# PB_ExtenderPlug.net
KiCad netlist of a schematic drawn in Altium Designer
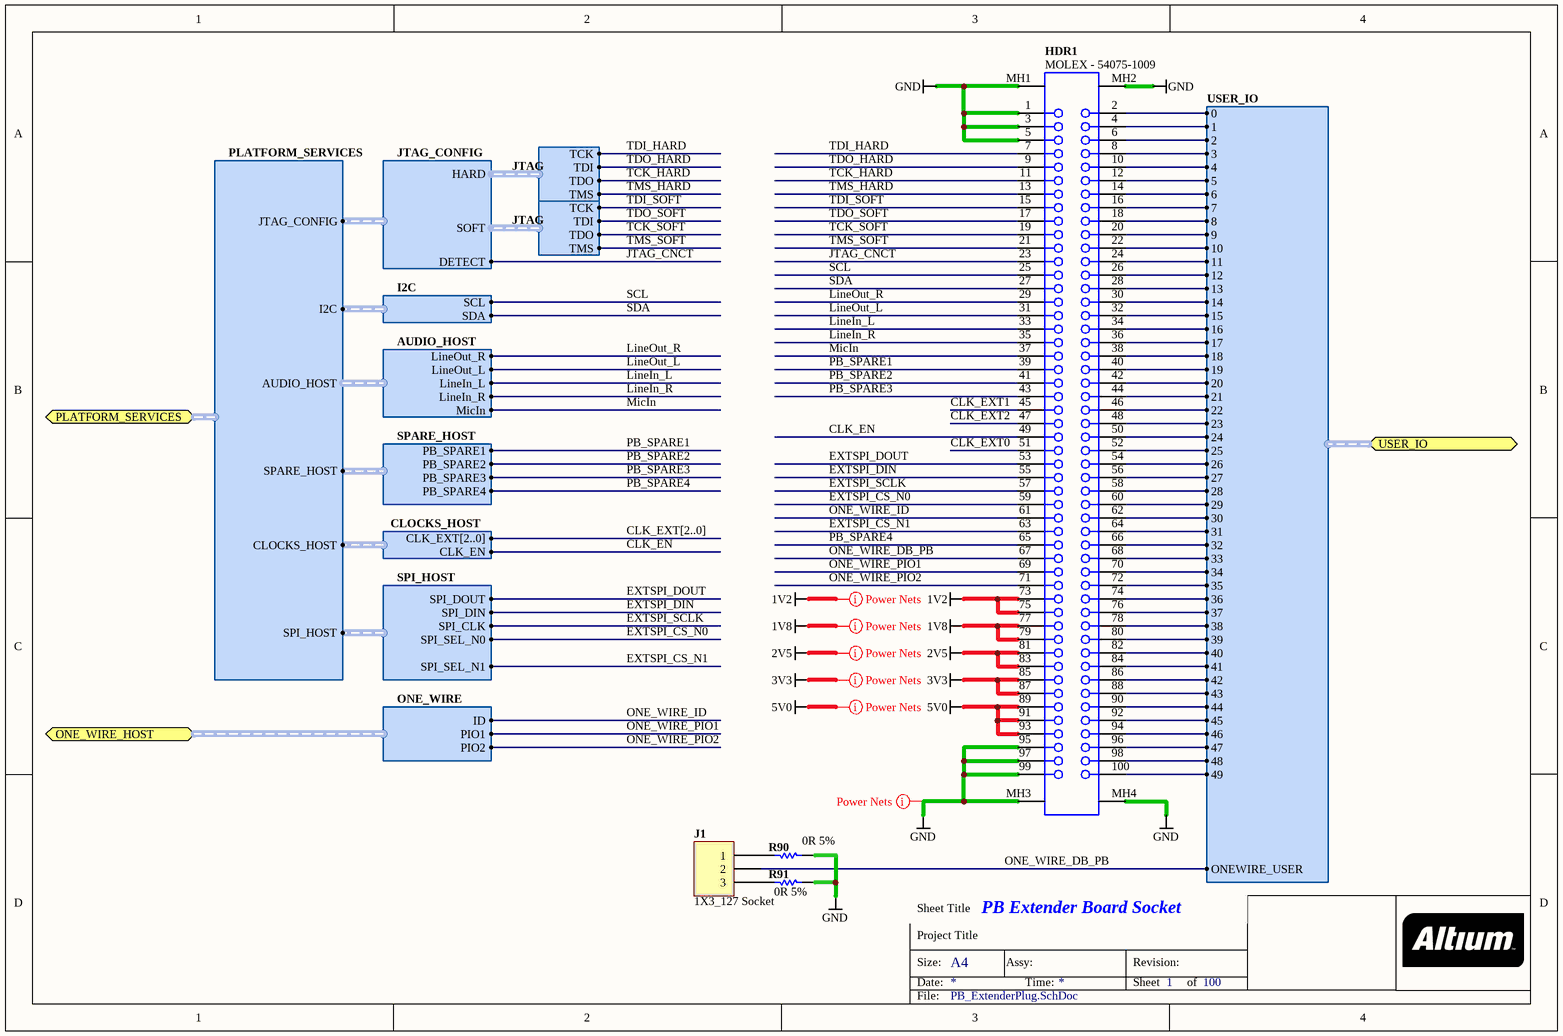
[diagram p0: PB_ExtenderPlug.SchDoc]

(export (version "E")
  (design (tool "Eeschema 10.0.6"))
  (components
    (comp (ref "HDR1")
      (value "MOLEX - 54075-1009")
      (footprint "54075")
      (description "Connector, Molex Docking Station 100 Pin Male 54075")
      (libsource (lib "AltiumDesignLibrary") (part "CON-DOCKSTAT-100-M-STR"))
    )
    (comp (ref "J1")
      (value "1X3_127 Socket")
      (footprint "MHDR1X3_127")
      (description "1X3 Pin Vert 1.27mm Socket")
      (fields (field (name "PUBLISHER") "Altium Limited"))
      (libsource (lib "AltiumDesignLibrary") (part "MHDR1X3_127"))
    )
    (comp (ref "R90")
      (value "0R 5%")
      (footprint "RESC1005-STAR")
      (description "Resistor, 0R 5% 0402 (1005)")
      (fields (field (name "TOLERANCE") "5 %"))
      (libsource (lib "AltiumDesignLibrary") (part "RES"))
    )
    (comp (ref "R91")
      (value "0R 5%")
      (footprint "RESC1005-STAR")
      (description "Resistor, 0R 5% 0402 (1005)")
      (fields (field (name "TOLERANCE") "5 %"))
      (libsource (lib "AltiumDesignLibrary") (part "RES"))
    )
  )
  (nets
    (net (code "10") (name "/0") (class "Default")
      (node (ref "HDR1") (pin "2") (pinfunction "2_2") (pintype "passive"))
    )
    (net (code "11") (name "/1") (class "Default")
      (node (ref "HDR1") (pin "4") (pinfunction "4_4") (pintype "passive"))
    )
    (net (code "12") (name "/2") (class "Default")
      (node (ref "HDR1") (pin "6") (pinfunction "6_6") (pintype "passive"))
    )
    (net (code "13") (name "/3") (class "Default")
      (node (ref "HDR1") (pin "8") (pinfunction "8_8") (pintype "passive"))
    )
    (net (code "14") (name "/4") (class "Default")
      (node (ref "HDR1") (pin "10") (pinfunction "10_10") (pintype "passive"))
    )
    (net (code "15") (name "/5") (class "Default")
      (node (ref "HDR1") (pin "12") (pinfunction "12_12") (pintype "passive"))
    )
    (net (code "16") (name "/6") (class "Default")
      (node (ref "HDR1") (pin "14") (pinfunction "14_14") (pintype "passive"))
    )
    (net (code "17") (name "/7") (class "Default")
      (node (ref "HDR1") (pin "16") (pinfunction "16_16") (pintype "passive"))
    )
    (net (code "18") (name "/8") (class "Default")
      (node (ref "HDR1") (pin "18") (pinfunction "18_18") (pintype "passive"))
    )
    (net (code "19") (name "/9") (class "Default")
      (node (ref "HDR1") (pin "20") (pinfunction "20_20") (pintype "passive"))
    )
    (net (code "20") (name "/10") (class "Default")
      (node (ref "HDR1") (pin "22") (pinfunction "22_22") (pintype "passive"))
    )
    (net (code "21") (name "/11") (class "Default")
      (node (ref "HDR1") (pin "24") (pinfunction "24_24") (pintype "passive"))
    )
    (net (code "22") (name "/12") (class "Default")
      (node (ref "HDR1") (pin "26") (pinfunction "26_26") (pintype "passive"))
    )
    (net (code "23") (name "/13") (class "Default")
      (node (ref "HDR1") (pin "28") (pinfunction "28_28") (pintype "passive"))
    )
    (net (code "24") (name "/14") (class "Default")
      (node (ref "HDR1") (pin "30") (pinfunction "30_30") (pintype "passive"))
    )
    (net (code "25") (name "/15") (class "Default")
      (node (ref "HDR1") (pin "32") (pinfunction "32_32") (pintype "passive"))
    )
    (net (code "26") (name "/16") (class "Default")
      (node (ref "HDR1") (pin "34") (pinfunction "34_34") (pintype "passive"))
    )
    (net (code "27") (name "/17") (class "Default")
      (node (ref "HDR1") (pin "36") (pinfunction "36_36") (pintype "passive"))
    )
    (net (code "28") (name "/18") (class "Default")
      (node (ref "HDR1") (pin "38") (pinfunction "38_38") (pintype "passive"))
    )
    (net (code "29") (name "/19") (class "Default")
      (node (ref "HDR1") (pin "40") (pinfunction "40_40") (pintype "passive"))
    )
    (net (code "30") (name "/20") (class "Default")
      (node (ref "HDR1") (pin "42") (pinfunction "42_42") (pintype "passive"))
    )
    (net (code "31") (name "/21") (class "Default")
      (node (ref "HDR1") (pin "44") (pinfunction "44_44") (pintype "passive"))
    )
    (net (code "32") (name "/22") (class "Default")
      (node (ref "HDR1") (pin "46") (pinfunction "46_46") (pintype "passive"))
    )
    (net (code "33") (name "/23") (class "Default")
      (node (ref "HDR1") (pin "48") (pinfunction "48_48") (pintype "passive"))
    )
    (net (code "34") (name "/24") (class "Default")
      (node (ref "HDR1") (pin "50") (pinfunction "50_50") (pintype "passive"))
    )
    (net (code "35") (name "/25") (class "Default")
      (node (ref "HDR1") (pin "52") (pinfunction "52_52") (pintype "passive"))
    )
    (net (code "36") (name "/26") (class "Default")
      (node (ref "HDR1") (pin "54") (pinfunction "54_54") (pintype "passive"))
    )
    (net (code "37") (name "/27") (class "Default")
      (node (ref "HDR1") (pin "56") (pinfunction "56_56") (pintype "passive"))
    )
    (net (code "38") (name "/28") (class "Default")
      (node (ref "HDR1") (pin "58") (pinfunction "58_58") (pintype "passive"))
    )
    (net (code "39") (name "/29") (class "Default")
      (node (ref "HDR1") (pin "60") (pinfunction "60_60") (pintype "passive"))
    )
    (net (code "40") (name "/30") (class "Default")
      (node (ref "HDR1") (pin "62") (pinfunction "62_62") (pintype "passive"))
    )
    (net (code "41") (name "/31") (class "Default")
      (node (ref "HDR1") (pin "64") (pinfunction "64_64") (pintype "passive"))
    )
    (net (code "42") (name "/32") (class "Default")
      (node (ref "HDR1") (pin "66") (pinfunction "66_66") (pintype "passive"))
    )
    (net (code "43") (name "/33") (class "Default")
      (node (ref "HDR1") (pin "68") (pinfunction "68_68") (pintype "passive"))
    )
    (net (code "44") (name "/34") (class "Default")
      (node (ref "HDR1") (pin "70") (pinfunction "70_70") (pintype "passive"))
    )
    (net (code "45") (name "/35") (class "Default")
      (node (ref "HDR1") (pin "72") (pinfunction "72_72") (pintype "passive"))
    )
    (net (code "46") (name "/36") (class "Default")
      (node (ref "HDR1") (pin "74") (pinfunction "74_74") (pintype "passive"))
    )
    (net (code "47") (name "/37") (class "Default")
      (node (ref "HDR1") (pin "76") (pinfunction "76_76") (pintype "passive"))
    )
    (net (code "48") (name "/38") (class "Default")
      (node (ref "HDR1") (pin "78") (pinfunction "78_78") (pintype "passive"))
    )
    (net (code "49") (name "/39") (class "Default")
      (node (ref "HDR1") (pin "80") (pinfunction "80_80") (pintype "passive"))
    )
    (net (code "50") (name "/40") (class "Default")
      (node (ref "HDR1") (pin "82") (pinfunction "82_82") (pintype "passive"))
    )
    (net (code "51") (name "/41") (class "Default")
      (node (ref "HDR1") (pin "84") (pinfunction "84_84") (pintype "passive"))
    )
    (net (code "52") (name "/42") (class "Default")
      (node (ref "HDR1") (pin "86") (pinfunction "86_86") (pintype "passive"))
    )
    (net (code "53") (name "/43") (class "Default")
      (node (ref "HDR1") (pin "88") (pinfunction "88_88") (pintype "passive"))
    )
    (net (code "54") (name "/44") (class "Default")
      (node (ref "HDR1") (pin "90") (pinfunction "90_90") (pintype "passive"))
    )
    (net (code "55") (name "/45") (class "Default")
      (node (ref "HDR1") (pin "92") (pinfunction "92_92") (pintype "passive"))
    )
    (net (code "56") (name "/46") (class "Default")
      (node (ref "HDR1") (pin "94") (pinfunction "94_94") (pintype "passive"))
    )
    (net (code "57") (name "/47") (class "Default")
      (node (ref "HDR1") (pin "96") (pinfunction "96_96") (pintype "passive"))
    )
    (net (code "58") (name "/48") (class "Default")
      (node (ref "HDR1") (pin "98") (pinfunction "98_98") (pintype "passive"))
    )
    (net (code "59") (name "/49") (class "Default")
      (node (ref "HDR1") (pin "100") (pinfunction "100_100") (pintype "passive"))
    )
    (net (code "60") (name "/CLK_EN") (class "Default")
      (node (ref "HDR1") (pin "49") (pinfunction "49_49") (pintype "passive"))
    )
    (net (code "61") (name "/CLK_EXT0") (class "Default")
      (node (ref "HDR1") (pin "51") (pinfunction "51_51") (pintype "passive"))
    )
    (net (code "62") (name "/CLK_EXT1") (class "Default")
      (node (ref "HDR1") (pin "45") (pinfunction "45_45") (pintype "passive"))
    )
    (net (code "63") (name "/CLK_EXT2") (class "Default")
      (node (ref "HDR1") (pin "47") (pinfunction "47_47") (pintype "passive"))
    )
    (net (code "65") (name "/EXTSPI_CS_N0") (class "Default")
      (node (ref "HDR1") (pin "59") (pinfunction "59_59") (pintype "passive"))
    )
    (net (code "66") (name "/EXTSPI_CS_N1") (class "Default")
      (node (ref "HDR1") (pin "63") (pinfunction "63_63") (pintype "passive"))
    )
    (net (code "67") (name "/EXTSPI_DIN") (class "Default")
      (node (ref "HDR1") (pin "55") (pinfunction "55_55") (pintype "passive"))
    )
    (net (code "68") (name "/EXTSPI_DOUT") (class "Default")
      (node (ref "HDR1") (pin "53") (pinfunction "53_53") (pintype "passive"))
    )
    (net (code "69") (name "/EXTSPI_SCLK") (class "Default")
      (node (ref "HDR1") (pin "57") (pinfunction "57_57") (pintype "passive"))
    )
    (net (code "70") (name "/JTAG_CNCT") (class "Default")
      (node (ref "HDR1") (pin "23") (pinfunction "23_23") (pintype "passive"))
    )
    (net (code "71") (name "/LineIn_L") (class "Default")
      (node (ref "HDR1") (pin "33") (pinfunction "33_33") (pintype "passive"))
    )
    (net (code "72") (name "/LineIn_R") (class "Default")
      (node (ref "HDR1") (pin "35") (pinfunction "35_35") (pintype "passive"))
    )
    (net (code "73") (name "/LineOut_L") (class "Default")
      (node (ref "HDR1") (pin "31") (pinfunction "31_31") (pintype "passive"))
    )
    (net (code "74") (name "/LineOut_R") (class "Default")
      (node (ref "HDR1") (pin "29") (pinfunction "29_29") (pintype "passive"))
    )
    (net (code "75") (name "/MicIn") (class "Default")
      (node (ref "HDR1") (pin "37") (pinfunction "37_37") (pintype "passive"))
    )
    (net (code "76") (name "/ONE_WIRE_DB_PB") (class "Default")
      (node (ref "HDR1") (pin "67") (pinfunction "67_67") (pintype "passive"))
      (node (ref "J1") (pin "2") (pinfunction "2_2") (pintype "passive"))
    )
    (net (code "77") (name "/ONE_WIRE_ID") (class "Default")
      (node (ref "HDR1") (pin "61") (pinfunction "61_61") (pintype "passive"))
    )
    (net (code "78") (name "/ONE_WIRE_PIO1") (class "Default")
      (node (ref "HDR1") (pin "69") (pinfunction "69_69") (pintype "passive"))
    )
    (net (code "79") (name "/ONE_WIRE_PIO2") (class "Default")
      (node (ref "HDR1") (pin "71") (pinfunction "71_71") (pintype "passive"))
    )
    (net (code "80") (name "/PB_SPARE1") (class "Default")
      (node (ref "HDR1") (pin "39") (pinfunction "39_39") (pintype "passive"))
    )
    (net (code "81") (name "/PB_SPARE2") (class "Default")
      (node (ref "HDR1") (pin "41") (pinfunction "41_41") (pintype "passive"))
    )
    (net (code "82") (name "/PB_SPARE3") (class "Default")
      (node (ref "HDR1") (pin "43") (pinfunction "43_43") (pintype "passive"))
    )
    (net (code "83") (name "/PB_SPARE4") (class "Default")
      (node (ref "HDR1") (pin "65") (pinfunction "65_65") (pintype "passive"))
    )
    (net (code "84") (name "/SCL") (class "Default")
      (node (ref "HDR1") (pin "25") (pinfunction "25_25") (pintype "passive"))
    )
    (net (code "85") (name "/SDA") (class "Default")
      (node (ref "HDR1") (pin "27") (pinfunction "27_27") (pintype "passive"))
    )
    (net (code "86") (name "/TCK_HARD") (class "Default")
      (node (ref "HDR1") (pin "11") (pinfunction "11_11") (pintype "passive"))
    )
    (net (code "87") (name "/TCK_SOFT") (class "Default")
      (node (ref "HDR1") (pin "19") (pinfunction "19_19") (pintype "passive"))
    )
    (net (code "88") (name "/TDI_HARD") (class "Default")
      (node (ref "HDR1") (pin "7") (pinfunction "7_7") (pintype "passive"))
    )
    (net (code "89") (name "/TDI_SOFT") (class "Default")
      (node (ref "HDR1") (pin "15") (pinfunction "15_15") (pintype "passive"))
    )
    (net (code "90") (name "/TDO_HARD") (class "Default")
      (node (ref "HDR1") (pin "9") (pinfunction "9_9") (pintype "passive"))
    )
    (net (code "91") (name "/TDO_SOFT") (class "Default")
      (node (ref "HDR1") (pin "17") (pinfunction "17_17") (pintype "passive"))
    )
    (net (code "92") (name "/TMS_HARD") (class "Default")
      (node (ref "HDR1") (pin "13") (pinfunction "13_13") (pintype "passive"))
    )
    (net (code "93") (name "/TMS_SOFT") (class "Default")
      (node (ref "HDR1") (pin "21") (pinfunction "21_21") (pintype "passive"))
    )
    (net (code "103") (name "1V2") (class "Default")
      (node (ref "HDR1") (pin "73") (pinfunction "73_73") (pintype "passive"))
      (node (ref "HDR1") (pin "75") (pinfunction "75_75") (pintype "passive"))
    )
    (net (code "104") (name "1V8") (class "Default")
      (node (ref "HDR1") (pin "77") (pinfunction "77_77") (pintype "passive"))
      (node (ref "HDR1") (pin "79") (pinfunction "79_79") (pintype "passive"))
    )
    (net (code "105") (name "2V5") (class "Default")
      (node (ref "HDR1") (pin "81") (pinfunction "81_81") (pintype "passive"))
      (node (ref "HDR1") (pin "83") (pinfunction "83_83") (pintype "passive"))
    )
    (net (code "106") (name "3V3") (class "Default")
      (node (ref "HDR1") (pin "85") (pinfunction "85_85") (pintype "passive"))
      (node (ref "HDR1") (pin "87") (pinfunction "87_87") (pintype "passive"))
    )
    (net (code "107") (name "5V0") (class "Default")
      (node (ref "HDR1") (pin "89") (pinfunction "89_89") (pintype "passive"))
      (node (ref "HDR1") (pin "91") (pinfunction "91_91") (pintype "passive"))
      (node (ref "HDR1") (pin "93") (pinfunction "93_93") (pintype "passive"))
    )
    (net (code "108") (name "GND") (class "Default")
      (node (ref "HDR1") (pin "1") (pinfunction "1_1") (pintype "passive"))
      (node (ref "HDR1") (pin "3") (pinfunction "3_3") (pintype "passive"))
      (node (ref "HDR1") (pin "5") (pinfunction "5_5") (pintype "passive"))
      (node (ref "HDR1") (pin "95") (pinfunction "95_95") (pintype "passive"))
      (node (ref "HDR1") (pin "97") (pinfunction "97_97") (pintype "passive"))
      (node (ref "HDR1") (pin "99") (pinfunction "99_99") (pintype "passive"))
      (node (ref "HDR1") (pin "MH1") (pinfunction "MH1_MH1") (pintype "passive"))
      (node (ref "HDR1") (pin "MH2") (pinfunction "MH2_MH2") (pintype "passive"))
      (node (ref "HDR1") (pin "MH3") (pinfunction "MH3_MH3") (pintype "passive"))
      (node (ref "HDR1") (pin "MH4") (pinfunction "MH4_MH4") (pintype "passive"))
      (node (ref "R90") (pin "2") (pinfunction "2_2") (pintype "passive"))
      (node (ref "R91") (pin "2") (pinfunction "2_2") (pintype "passive"))
    )
    (net (code "109") (name "Net-(J1-Pad1)") (class "Default")
      (node (ref "J1") (pin "1") (pinfunction "1_1") (pintype "passive"))
      (node (ref "R90") (pin "1") (pinfunction "1_1") (pintype "passive"))
    )
    (net (code "110") (name "Net-(J1-Pad3)") (class "Default")
      (node (ref "J1") (pin "3") (pinfunction "3_3") (pintype "passive"))
      (node (ref "R91") (pin "1") (pinfunction "1_1") (pintype "passive"))
    )
  )
)
